# 02_Power1.net
KiCad netlist of a schematic drawn in Altium Designer
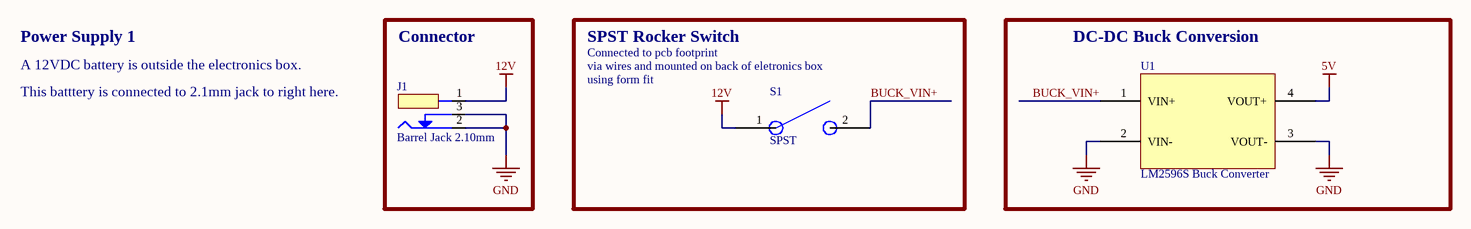
[diagram p0: 02_Power1.SchDoc]

(export (version "E")
  (design (tool "Eeschema 10.0.6"))
  (components
    (comp (ref "J1")
      (value "Barrel Jack 2.10mm")
      (footprint "2.1mm Barrel Jack Connector")
      (description "Power Barrel Connector Jack 2.10mm ID (0.083\"), 5.50mm OD (0.217\") Through Hole, Right Angle")
      (fields (field (name "MANUFACTURER") "Tensility") (field (name "MANUFACTURER PART NUMBER") "54-00133"))
      (libsource (lib "Ground Support_Schlib") (part "54-00133"))
    )
    (comp (ref "S1")
      (value "SPST")
      (footprint "SPST Switch")
      (description "SPST Switch")
      (libsource (lib "Ground Support_Schlib") (part "SPST Switch"))
    )
    (comp (ref "U1")
      (value "LM2596S Buck Converter")
      (footprint "LM2596S Buck Converter")
      (fields
        (field (name "MANUFACTURER") "Frienda")
        (field (name "MANUFACTURER PART NUMBER") "Frienda-Power Converters-01")
      )
      (libsource (lib "Ground Support_Schlib") (part "LM2596S Buck Converter"))
    )
  )
  (nets
    (net (code "1") (name "/BUCK_VIN+") (class "Default")
      (node (ref "S1") (pin "2") (pinfunction "-_2") (pintype "passive"))
      (node (ref "U1") (pin "1") (pinfunction "VIN+_1") (pintype "passive"))
    )
    (net (code "2") (name "5V") (class "Default")
      (node (ref "U1") (pin "4") (pinfunction "VOUT+_4") (pintype "passive"))
    )
    (net (code "3") (name "12V") (class "Default")
      (node (ref "J1") (pin "1") (pinfunction "1_1") (pintype "power_in"))
      (node (ref "S1") (pin "1") (pinfunction "+_1") (pintype "passive"))
    )
    (net (code "4") (name "GND") (class "Default")
      (node (ref "J1") (pin "2") (pinfunction "2_2") (pintype "power_in"))
      (node (ref "J1") (pin "3") (pinfunction "3_3") (pintype "power_in"))
      (node (ref "U1") (pin "2") (pinfunction "VIN-_2") (pintype "passive"))
      (node (ref "U1") (pin "3") (pinfunction "VOUT-_3") (pintype "passive"))
    )
  )
)
